# PSLVCommutationRobot.net
KiCad netlist of a schematic drawn in EAGLE
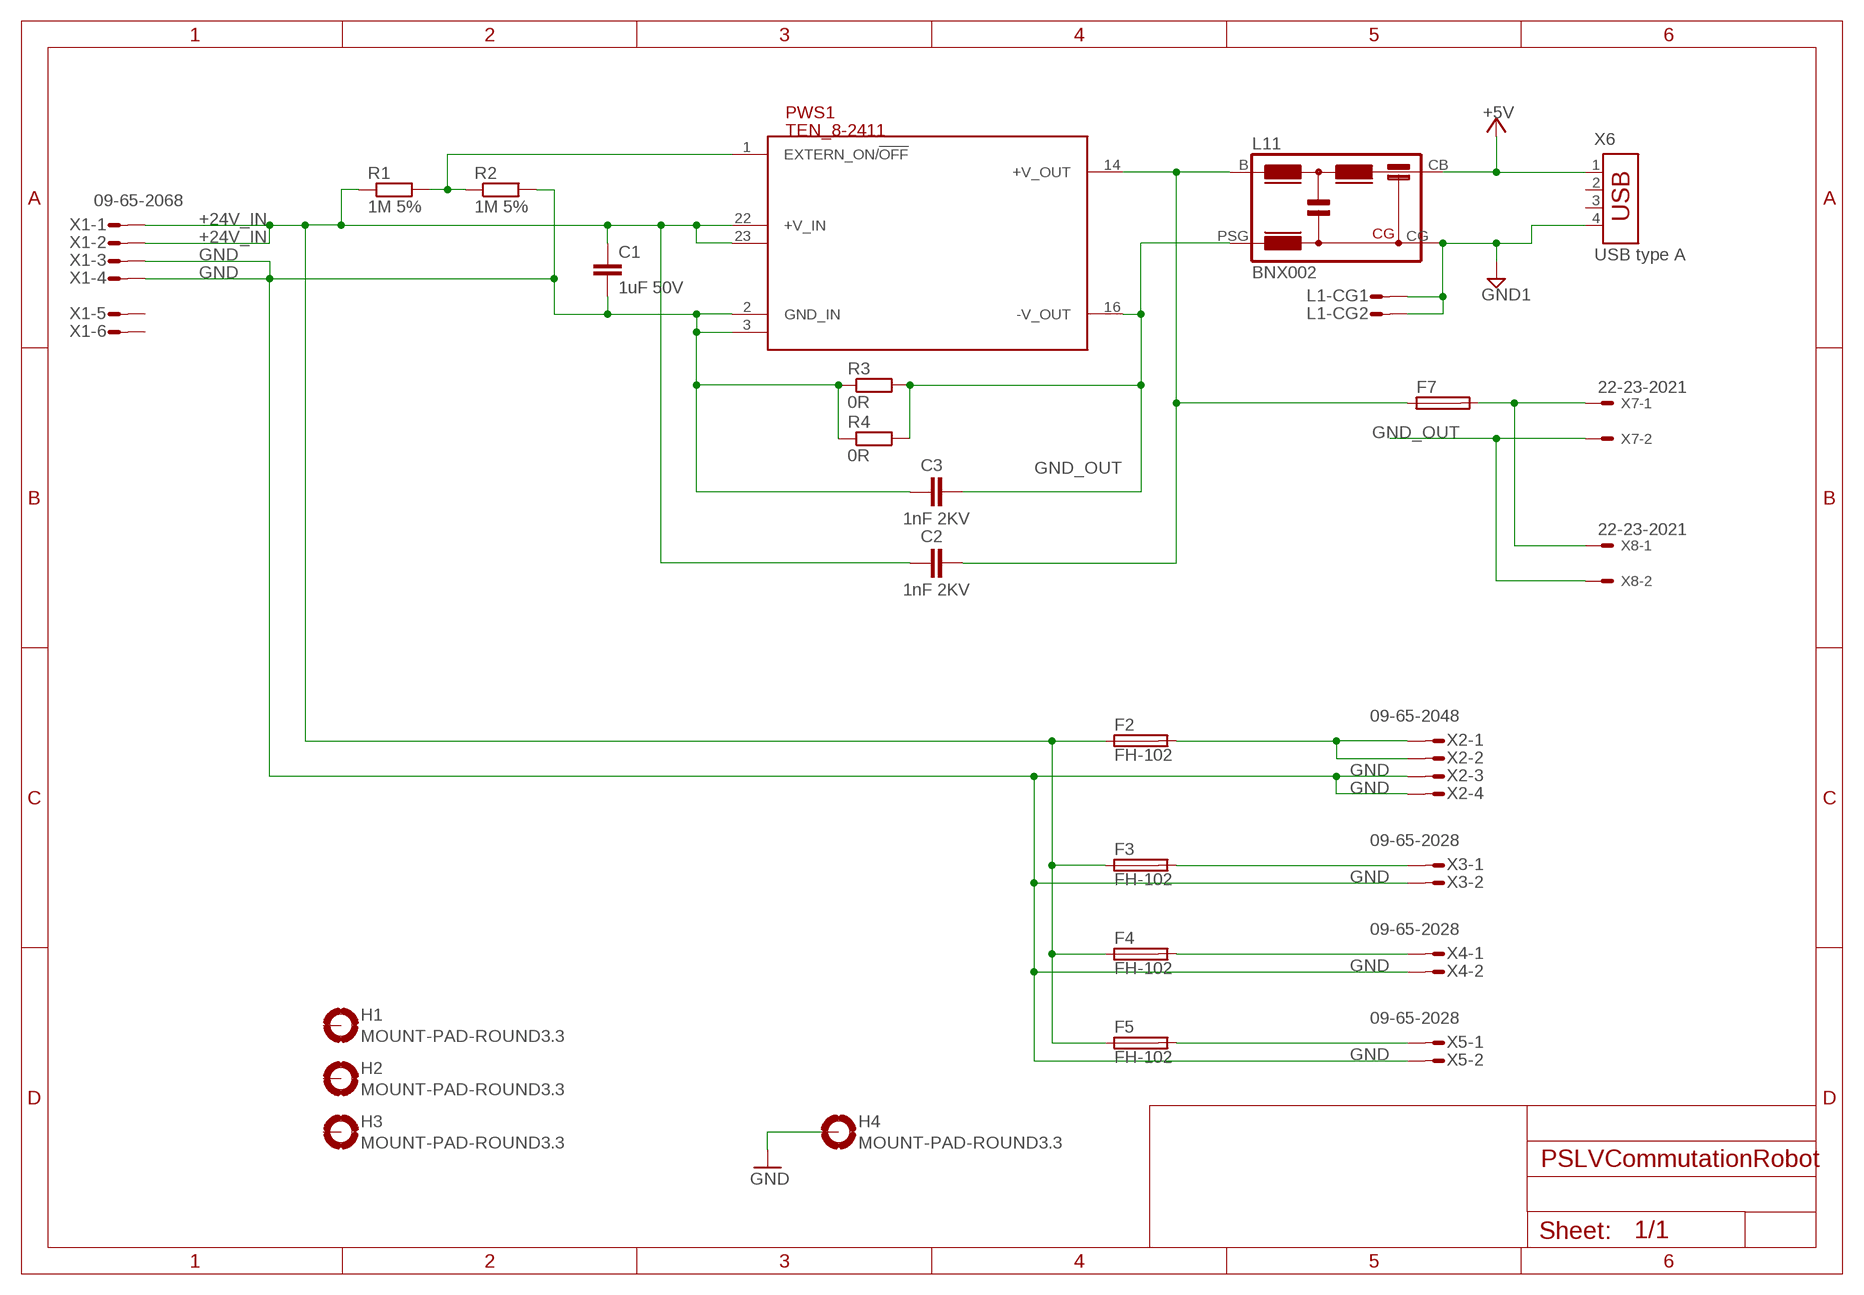
[diagram p0: schematic, sheet 1]

(export (version "E")
  (design (tool "Eeschema 10.0.6"))
  (components
    (comp (ref "C1")
      (value "1uF 50V")
      (footprint "eagle-import:C1210")
      (libsource (lib "eagle-import") (part "C-EUC1210"))
    )
    (comp (ref "C2")
      (value "1nF 2KV")
      (footprint "eagle-import:C1206")
      (libsource (lib "eagle-import") (part "C-EUC1206"))
    )
    (comp (ref "C3")
      (value "1nF 2KV")
      (footprint "eagle-import:C1206")
      (libsource (lib "eagle-import") (part "C-EUC1206"))
    )
    (comp (ref "F2")
      (value "FH-102")
      (footprint "eagle-import:SH22,5")
      (fields
        (field (name "MF") "SCHURTER")
        (field (name "MPN") "0031.8201")
        (field (name "MF_1") "SCHURTER")
        (field (name "MPN_1") "0031.8201")
        (field (name "OC_FARNELL") "1162740")
        (field (name "OC_NEWARK") "96F8317")
      )
      (libsource (lib "eagle-import") (part "SH22,5"))
    )
    (comp (ref "F3")
      (value "FH-102")
      (footprint "eagle-import:SH22,5")
      (fields
        (field (name "MF") "SCHURTER")
        (field (name "MPN") "0031.8201")
        (field (name "MF_1") "SCHURTER")
        (field (name "MPN_1") "0031.8201")
        (field (name "OC_FARNELL") "1162740")
        (field (name "OC_NEWARK") "96F8317")
      )
      (libsource (lib "eagle-import") (part "SH22,5"))
    )
    (comp (ref "F4")
      (value "FH-102")
      (footprint "eagle-import:SH22,5")
      (fields
        (field (name "MF") "SCHURTER")
        (field (name "MPN") "0031.8201")
        (field (name "MF_1") "SCHURTER")
        (field (name "MPN_1") "0031.8201")
        (field (name "OC_FARNELL") "1162740")
        (field (name "OC_NEWARK") "96F8317")
      )
      (libsource (lib "eagle-import") (part "SH22,5"))
    )
    (comp (ref "F5")
      (value "FH-102")
      (footprint "eagle-import:SH22,5")
      (fields
        (field (name "MF") "SCHURTER")
        (field (name "MPN") "0031.8201")
        (field (name "MF_1") "SCHURTER")
        (field (name "MPN_1") "0031.8201")
        (field (name "OC_FARNELL") "1162740")
        (field (name "OC_NEWARK") "96F8317")
      )
      (libsource (lib "eagle-import") (part "SH22,5"))
    )
    (comp (ref "F7")
      (value "SH22,5")
      (footprint "eagle-import:SH22,5")
      (fields
        (field (name "MF") "SCHURTER")
        (field (name "MPN") "0031.8201")
        (field (name "MF_1") "SCHURTER")
        (field (name "MPN_1") "0031.8201")
        (field (name "OC_FARNELL") "1162740")
        (field (name "OC_NEWARK") "96F8317")
      )
      (libsource (lib "eagle-import") (part "SH22,5"))
    )
    (comp (ref "H1")
      (value "MOUNT-PAD-ROUND3.3")
      (footprint "eagle-import:3,3-PAD")
      (libsource (lib "eagle-import") (part "MOUNT-PAD-ROUND3.3"))
    )
    (comp (ref "H2")
      (value "MOUNT-PAD-ROUND3.3")
      (footprint "eagle-import:3,3-PAD")
      (libsource (lib "eagle-import") (part "MOUNT-PAD-ROUND3.3"))
    )
    (comp (ref "H3")
      (value "MOUNT-PAD-ROUND3.3")
      (footprint "eagle-import:3,3-PAD")
      (libsource (lib "eagle-import") (part "MOUNT-PAD-ROUND3.3"))
    )
    (comp (ref "H4")
      (value "MOUNT-PAD-ROUND3.3")
      (footprint "eagle-import:3,3-PAD")
      (libsource (lib "eagle-import") (part "MOUNT-PAD-ROUND3.3"))
    )
    (comp (ref "L1")
      (value "BNX002")
      (footprint "eagle-import:BNX002")
      (libsource (lib "eagle-import") (part "BNX002"))
    )
    (comp (ref "PWS1")
      (value "TEN_8-2411")
      (footprint "eagle-import:TRACO_TEN_8_SERIE")
      (libsource (lib "eagle-import") (part "TRACO_TEN_8-2411"))
    )
    (comp (ref "R1")
      (value "1M 5%")
      (footprint "eagle-import:R1206")
      (libsource (lib "eagle-import") (part "R-EU_R1206"))
    )
    (comp (ref "R2")
      (value "1M 5%")
      (footprint "eagle-import:R1206")
      (libsource (lib "eagle-import") (part "R-EU_R1206"))
    )
    (comp (ref "R3")
      (value "0R")
      (footprint "eagle-import:R1206")
      (libsource (lib "eagle-import") (part "R-EU_R1206"))
    )
    (comp (ref "R4")
      (value "0R")
      (footprint "eagle-import:R1206")
      (libsource (lib "eagle-import") (part "R-EU_R1206"))
    )
    (comp (ref "X1")
      (value "09-65-2068")
      (footprint "eagle-import:MOLEX_09-65-2068")
      (libsource (lib "eagle-import") (part "MOLEX_09-65-2068"))
    )
    (comp (ref "X2")
      (value "09-65-2048")
      (footprint "eagle-import:MOLEX_09-65-2048")
      (libsource (lib "eagle-import") (part "MOLEX_09-65-2048"))
    )
    (comp (ref "X3")
      (value "09-65-2028")
      (footprint "eagle-import:MOLEX_09-65-2028")
      (libsource (lib "eagle-import") (part "MOLEX_09-65-2028"))
    )
    (comp (ref "X4")
      (value "09-65-2028")
      (footprint "eagle-import:MOLEX_09-65-2028")
      (libsource (lib "eagle-import") (part "MOLEX_09-65-2028"))
    )
    (comp (ref "X5")
      (value "09-65-2028")
      (footprint "eagle-import:MOLEX_09-65-2028")
      (libsource (lib "eagle-import") (part "MOLEX_09-65-2028"))
    )
    (comp (ref "X6")
      (value "USB type A")
      (footprint "eagle-import:USB")
      (libsource (lib "eagle-import") (part "USB-787616"))
    )
    (comp (ref "X7")
      (value "22-23-2021")
      (footprint "eagle-import:22-23-2021")
      (fields (field (name "MF") "MOLEX"))
      (libsource (lib "eagle-import") (part "22-23-2021"))
    )
    (comp (ref "X8")
      (value "22-23-2021")
      (footprint "eagle-import:22-23-2021")
      (fields (field (name "MF") "MOLEX"))
      (libsource (lib "eagle-import") (part "22-23-2021"))
    )
  )
  (nets
    (net (code "1") (name "+5V") (class "Default")
      (node (ref "L1") (pin "CB") (pinfunction "CB_CB") (pintype "passive"))
      (node (ref "X6") (pin "1") (pinfunction "1_1") (pintype "passive"))
    )
    (net (code "2") (name "/+24V_IN") (class "Default")
      (node (ref "C1") (pin "1") (pinfunction "1_1") (pintype "passive"))
      (node (ref "C2") (pin "1") (pinfunction "1_1") (pintype "passive"))
      (node (ref "F2") (pin "1") (pinfunction "1_1") (pintype "passive"))
      (node (ref "F3") (pin "1") (pinfunction "1_1") (pintype "passive"))
      (node (ref "F4") (pin "1") (pinfunction "1_1") (pintype "passive"))
      (node (ref "F5") (pin "1") (pinfunction "1_1") (pintype "passive"))
      (node (ref "PWS1") (pin "22") (pinfunction "+V_IN_22") (pintype "input"))
      (node (ref "PWS1") (pin "23") (pinfunction "+V_IN2_23") (pintype "input"))
      (node (ref "R1") (pin "1") (pinfunction "1_1") (pintype "passive"))
      (node (ref "X1") (pin "1") (pinfunction "S_1") (pintype "passive"))
      (node (ref "X1") (pin "2") (pinfunction "S_2") (pintype "passive"))
    )
    (net (code "3") (name "/GND_OUT") (class "Default")
      (node (ref "C3") (pin "2") (pinfunction "2_2") (pintype "passive"))
      (node (ref "L1") (pin "PSG") (pinfunction "PSG_PSG") (pintype "passive"))
      (node (ref "PWS1") (pin "16") (pinfunction "-V_OUT_16") (pintype "output"))
      (node (ref "R3") (pin "2") (pinfunction "2_2") (pintype "passive"))
      (node (ref "R4") (pin "2") (pinfunction "2_2") (pintype "passive"))
      (node (ref "X7") (pin "2") (pinfunction "S_2") (pintype "passive"))
      (node (ref "X8") (pin "2") (pinfunction "S_2") (pintype "passive"))
    )
    (net (code "4") (name "GND") (class "Default")
      (node (ref "C1") (pin "2") (pinfunction "2_2") (pintype "passive"))
      (node (ref "C3") (pin "1") (pinfunction "1_1") (pintype "passive"))
      (node (ref "H4") (pin "B3,3") (pinfunction "MOUNT_B3,3") (pintype "passive"))
      (node (ref "PWS1") (pin "2") (pinfunction "GND_IN_2") (pintype "input"))
      (node (ref "PWS1") (pin "3") (pinfunction "GND_IN2_3") (pintype "input"))
      (node (ref "R2") (pin "2") (pinfunction "2_2") (pintype "passive"))
      (node (ref "R3") (pin "1") (pinfunction "1_1") (pintype "passive"))
      (node (ref "R4") (pin "1") (pinfunction "1_1") (pintype "passive"))
      (node (ref "X1") (pin "3") (pinfunction "S_3") (pintype "passive"))
      (node (ref "X1") (pin "4") (pinfunction "S_4") (pintype "passive"))
      (node (ref "X2") (pin "3") (pinfunction "S_3") (pintype "passive"))
      (node (ref "X2") (pin "4") (pinfunction "S_4") (pintype "passive"))
      (node (ref "X3") (pin "2") (pinfunction "S_2") (pintype "passive"))
      (node (ref "X4") (pin "2") (pinfunction "S_2") (pintype "passive"))
      (node (ref "X5") (pin "2") (pinfunction "S_2") (pintype "passive"))
    )
    (net (code "5") (name "GND1") (class "Default")
      (node (ref "L1") (pin "CG") (pinfunction "CG_CG") (pintype "passive"))
      (node (ref "L1") (pin "CG1") (pinfunction "S_CG1") (pintype "passive"))
      (node (ref "L1") (pin "CG2") (pinfunction "S_CG2") (pintype "passive"))
      (node (ref "X6") (pin "4") (pinfunction "4_4") (pintype "passive"))
    )
    (net (code "6") (name "Net-(PWS1-+V_OUT)") (class "Default")
      (node (ref "C2") (pin "2") (pinfunction "2_2") (pintype "passive"))
      (node (ref "F7") (pin "1") (pinfunction "1_1") (pintype "passive"))
      (node (ref "L1") (pin "B") (pinfunction "B_B") (pintype "passive"))
      (node (ref "PWS1") (pin "14") (pinfunction "+V_OUT_14") (pintype "output"))
    )
    (net (code "7") (name "Net-(PWS1-EXTERN_ON{slash}~{OFF})") (class "Default")
      (node (ref "PWS1") (pin "1") (pinfunction "EXTERN_ON/~{OFF}_1") (pintype "input"))
      (node (ref "R1") (pin "2") (pinfunction "2_2") (pintype "passive"))
      (node (ref "R2") (pin "1") (pinfunction "1_1") (pintype "passive"))
    )
    (net (code "8") (name "Net-(X2A-S)") (class "Default")
      (node (ref "F2") (pin "2") (pinfunction "2_2") (pintype "passive"))
      (node (ref "X2") (pin "1") (pinfunction "S_1") (pintype "passive"))
      (node (ref "X2") (pin "2") (pinfunction "S_2") (pintype "passive"))
    )
    (net (code "9") (name "Net-(X3A-S)") (class "Default")
      (node (ref "F3") (pin "2") (pinfunction "2_2") (pintype "passive"))
      (node (ref "X3") (pin "1") (pinfunction "S_1") (pintype "passive"))
    )
    (net (code "10") (name "Net-(X4A-S)") (class "Default")
      (node (ref "F4") (pin "2") (pinfunction "2_2") (pintype "passive"))
      (node (ref "X4") (pin "1") (pinfunction "S_1") (pintype "passive"))
    )
    (net (code "11") (name "Net-(X5A-S)") (class "Default")
      (node (ref "F5") (pin "2") (pinfunction "2_2") (pintype "passive"))
      (node (ref "X5") (pin "1") (pinfunction "S_1") (pintype "passive"))
    )
    (net (code "12") (name "Net-(X7A-S)") (class "Default")
      (node (ref "F7") (pin "2") (pinfunction "2_2") (pintype "passive"))
      (node (ref "X7") (pin "1") (pinfunction "S_1") (pintype "passive"))
      (node (ref "X8") (pin "1") (pinfunction "S_1") (pintype "passive"))
    )
    (net (code "13") (name "unconnected-(H1-MOUNT-PadB3,3)") (class "Default")
      (node (ref "H1") (pin "B3,3") (pinfunction "MOUNT_B3,3") (pintype "passive"))
    )
    (net (code "14") (name "unconnected-(H2-MOUNT-PadB3,3)") (class "Default")
      (node (ref "H2") (pin "B3,3") (pinfunction "MOUNT_B3,3") (pintype "passive"))
    )
    (net (code "15") (name "unconnected-(H3-MOUNT-PadB3,3)") (class "Default")
      (node (ref "H3") (pin "B3,3") (pinfunction "MOUNT_B3,3") (pintype "passive"))
    )
    (net (code "16") (name "unconnected-(X1E-S-Pad5)") (class "Default")
      (node (ref "X1") (pin "5") (pinfunction "S_5") (pintype "passive"))
    )
    (net (code "17") (name "unconnected-(X1F-S-Pad6)") (class "Default")
      (node (ref "X1") (pin "6") (pinfunction "S_6") (pintype "passive"))
    )
    (net (code "18") (name "unconnected-(X6-Pad2)") (class "Default")
      (node (ref "X6") (pin "2") (pinfunction "2_2") (pintype "passive"))
    )
    (net (code "19") (name "unconnected-(X6-Pad3)") (class "Default")
      (node (ref "X6") (pin "3") (pinfunction "3_3") (pintype "passive"))
    )
  )
)
